# AOA-control-revC.net
KiCad netlist of a schematic drawn in EAGLE
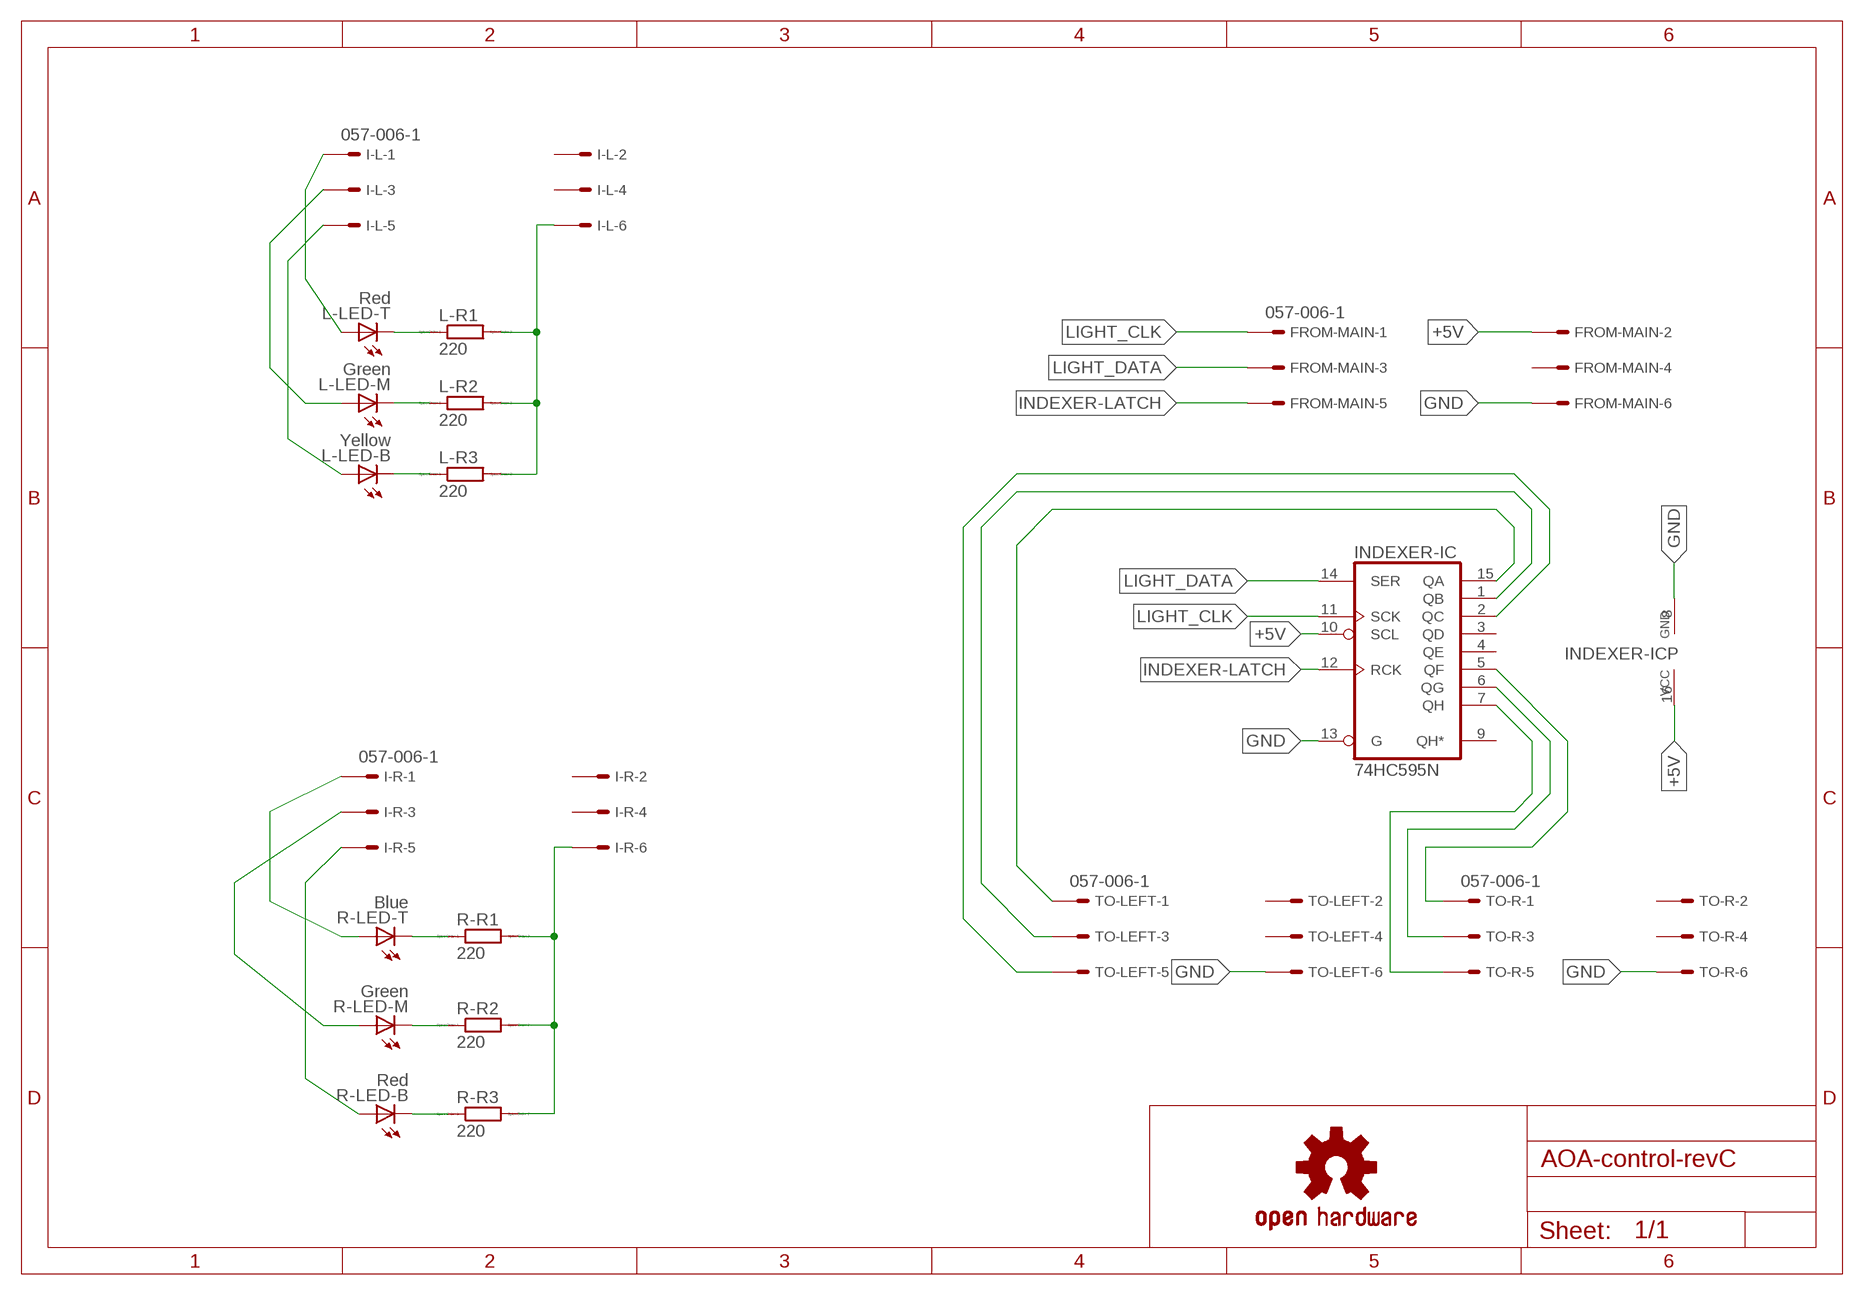
[diagram p0: schematic, sheet 1]

(export (version "E")
  (design (tool "Eeschema 10.0.6"))
  (components
    (comp (ref "FROM-MAIN")
      (value "057-006-1")
      (footprint "eagle-import:057-006-1")
      (libsource (lib "eagle-import") (part "057-006-1"))
    )
    (comp (ref "I-L")
      (value "057-006-1")
      (footprint "eagle-import:057-006-1")
      (libsource (lib "eagle-import") (part "057-006-1"))
    )
    (comp (ref "I-R")
      (value "057-006-1")
      (footprint "eagle-import:057-006-1")
      (libsource (lib "eagle-import") (part "057-006-1"))
    )
    (comp (ref "INDEXER-IC")
      (value "74HC595N")
      (footprint "eagle-import:DIL16")
      (libsource (lib "eagle-import") (part "74595NHC"))
    )
    (comp (ref "L-LED-B")
      (value "Yellow")
      (footprint "eagle-import:CP41B")
      (libsource (lib "eagle-import") (part "LED-2AC-CP41B-WGS"))
    )
    (comp (ref "L-LED-M")
      (value "Green")
      (footprint "eagle-import:CP41B")
      (libsource (lib "eagle-import") (part "LED-2AC-CP41B-WGS"))
    )
    (comp (ref "L-LED-T")
      (value "Red")
      (footprint "eagle-import:CP41B")
      (libsource (lib "eagle-import") (part "LED-2AC-CP41B-WGS"))
    )
    (comp (ref "L-R1")
      (value "220")
      (footprint "eagle-import:0204_7")
      (libsource (lib "eagle-import") (part "R0204/7"))
    )
    (comp (ref "L-R2")
      (value "220")
      (footprint "eagle-import:0204_7")
      (libsource (lib "eagle-import") (part "R0204/7"))
    )
    (comp (ref "L-R3")
      (value "220")
      (footprint "eagle-import:0204_7")
      (libsource (lib "eagle-import") (part "R0204/7"))
    )
    (comp (ref "LOGO1")
      (value "OSHW-LOGOS")
      (footprint "eagle-import:OSHW-LOGO-S")
      (libsource (lib "eagle-import") (part "OSHW-LOGOS"))
    )
    (comp (ref "R-LED-B")
      (value "Red")
      (footprint "eagle-import:CP41B")
      (libsource (lib "eagle-import") (part "LED-2AC-CP41B-WGS"))
    )
    (comp (ref "R-LED-M")
      (value "Green")
      (footprint "eagle-import:CP41B")
      (libsource (lib "eagle-import") (part "LED-2AC-CP41B-WGS"))
    )
    (comp (ref "R-LED-T")
      (value "Blue")
      (footprint "eagle-import:CP41B")
      (libsource (lib "eagle-import") (part "LED-2AC-CP41B-WGS"))
    )
    (comp (ref "R-R1")
      (value "220")
      (footprint "eagle-import:0204_7")
      (libsource (lib "eagle-import") (part "R0204/7"))
    )
    (comp (ref "R-R2")
      (value "220")
      (footprint "eagle-import:0204_7")
      (libsource (lib "eagle-import") (part "R0204/7"))
    )
    (comp (ref "R-R3")
      (value "220")
      (footprint "eagle-import:0204_7")
      (libsource (lib "eagle-import") (part "R0204/7"))
    )
    (comp (ref "TO-LEFT")
      (value "057-006-1")
      (footprint "eagle-import:057-006-1")
      (libsource (lib "eagle-import") (part "057-006-1"))
    )
    (comp (ref "TO-R")
      (value "057-006-1")
      (footprint "eagle-import:057-006-1")
      (libsource (lib "eagle-import") (part "057-006-1"))
    )
  )
  (nets
    (net (code "1") (name "+5V") (class "Default")
      (node (ref "FROM-MAIN") (pin "2") (pinfunction "S_2") (pintype "passive"))
      (node (ref "INDEXER-IC") (pin "10") (pinfunction "SCL_10") (pintype "input"))
      (node (ref "INDEXER-IC") (pin "16") (pinfunction "VCC_16") (pintype "power_in"))
    )
    (net (code "2") (name "GND") (class "Default")
      (node (ref "FROM-MAIN") (pin "6") (pinfunction "S_6") (pintype "passive"))
      (node (ref "I-L") (pin "6") (pinfunction "S_6") (pintype "passive"))
      (node (ref "I-R") (pin "6") (pinfunction "S_6") (pintype "passive"))
      (node (ref "INDEXER-IC") (pin "13") (pinfunction "G_13") (pintype "input"))
      (node (ref "INDEXER-IC") (pin "8") (pinfunction "GND_8") (pintype "power_in"))
      (node (ref "L-R1") (pin "2") (pinfunction "2_2") (pintype "passive"))
      (node (ref "L-R2") (pin "2") (pinfunction "2_2") (pintype "passive"))
      (node (ref "L-R3") (pin "2") (pinfunction "2_2") (pintype "passive"))
      (node (ref "R-R1") (pin "2") (pinfunction "2_2") (pintype "passive"))
      (node (ref "R-R2") (pin "2") (pinfunction "2_2") (pintype "passive"))
      (node (ref "R-R3") (pin "2") (pinfunction "2_2") (pintype "passive"))
      (node (ref "TO-LEFT") (pin "6") (pinfunction "S_6") (pintype "passive"))
      (node (ref "TO-R") (pin "6") (pinfunction "S_6") (pintype "passive"))
    )
    (net (code "3") (name "INDEXER-LATCH") (class "Default")
      (node (ref "FROM-MAIN") (pin "5") (pinfunction "S_5") (pintype "passive"))
      (node (ref "INDEXER-IC") (pin "12") (pinfunction "RCK_12") (pintype "input"))
    )
    (net (code "4") (name "LIGHT_CLK") (class "Default")
      (node (ref "FROM-MAIN") (pin "1") (pinfunction "S_1") (pintype "passive"))
      (node (ref "INDEXER-IC") (pin "11") (pinfunction "SCK_11") (pintype "input"))
    )
    (net (code "5") (name "LIGHT_DATA") (class "Default")
      (node (ref "FROM-MAIN") (pin "3") (pinfunction "S_3") (pintype "passive"))
      (node (ref "INDEXER-IC") (pin "14") (pinfunction "SER_14") (pintype "input"))
    )
    (net (code "6") (name "Net-(I-LA-S)") (class "Default")
      (node (ref "I-L") (pin "1") (pinfunction "S_1") (pintype "passive"))
      (node (ref "L-LED-T") (pin "2") (pinfunction "A_2") (pintype "passive"))
      (node (ref "L-LED-T") (pin "3") (pinfunction "A_3") (pintype "passive"))
    )
    (net (code "7") (name "Net-(I-LC-S)") (class "Default")
      (node (ref "I-L") (pin "3") (pinfunction "S_3") (pintype "passive"))
      (node (ref "L-LED-M") (pin "2") (pinfunction "A_2") (pintype "passive"))
      (node (ref "L-LED-M") (pin "3") (pinfunction "A_3") (pintype "passive"))
    )
    (net (code "8") (name "Net-(I-LE-S)") (class "Default")
      (node (ref "I-L") (pin "5") (pinfunction "S_5") (pintype "passive"))
      (node (ref "L-LED-B") (pin "2") (pinfunction "A_2") (pintype "passive"))
      (node (ref "L-LED-B") (pin "3") (pinfunction "A_3") (pintype "passive"))
    )
    (net (code "9") (name "Net-(I-RA-S)") (class "Default")
      (node (ref "I-R") (pin "1") (pinfunction "S_1") (pintype "passive"))
      (node (ref "R-LED-T") (pin "2") (pinfunction "A_2") (pintype "passive"))
      (node (ref "R-LED-T") (pin "3") (pinfunction "A_3") (pintype "passive"))
    )
    (net (code "10") (name "Net-(I-RC-S)") (class "Default")
      (node (ref "I-R") (pin "3") (pinfunction "S_3") (pintype "passive"))
      (node (ref "R-LED-M") (pin "2") (pinfunction "A_2") (pintype "passive"))
      (node (ref "R-LED-M") (pin "3") (pinfunction "A_3") (pintype "passive"))
    )
    (net (code "11") (name "Net-(I-RE-S)") (class "Default")
      (node (ref "I-R") (pin "5") (pinfunction "S_5") (pintype "passive"))
      (node (ref "R-LED-B") (pin "2") (pinfunction "A_2") (pintype "passive"))
      (node (ref "R-LED-B") (pin "3") (pinfunction "A_3") (pintype "passive"))
    )
    (net (code "12") (name "Net-(INDEXER-ICA-QA)") (class "Default")
      (node (ref "INDEXER-IC") (pin "15") (pinfunction "QA_15") (pintype "tri_state"))
      (node (ref "TO-LEFT") (pin "1") (pinfunction "S_1") (pintype "passive"))
    )
    (net (code "13") (name "Net-(INDEXER-ICA-QB)") (class "Default")
      (node (ref "INDEXER-IC") (pin "1") (pinfunction "QB_1") (pintype "tri_state"))
      (node (ref "TO-LEFT") (pin "3") (pinfunction "S_3") (pintype "passive"))
    )
    (net (code "14") (name "Net-(INDEXER-ICA-QC)") (class "Default")
      (node (ref "INDEXER-IC") (pin "2") (pinfunction "QC_2") (pintype "tri_state"))
      (node (ref "TO-LEFT") (pin "5") (pinfunction "S_5") (pintype "passive"))
    )
    (net (code "15") (name "Net-(INDEXER-ICA-QF)") (class "Default")
      (node (ref "INDEXER-IC") (pin "5") (pinfunction "QF_5") (pintype "tri_state"))
      (node (ref "TO-R") (pin "1") (pinfunction "S_1") (pintype "passive"))
    )
    (net (code "16") (name "Net-(INDEXER-ICA-QG)") (class "Default")
      (node (ref "INDEXER-IC") (pin "6") (pinfunction "QG_6") (pintype "tri_state"))
      (node (ref "TO-R") (pin "3") (pinfunction "S_3") (pintype "passive"))
    )
    (net (code "17") (name "Net-(INDEXER-ICA-QH)") (class "Default")
      (node (ref "INDEXER-IC") (pin "7") (pinfunction "QH_7") (pintype "tri_state"))
      (node (ref "TO-R") (pin "5") (pinfunction "S_5") (pintype "passive"))
    )
    (net (code "18") (name "Net-(L-LED-B-C-Pad1)") (class "Default")
      (node (ref "L-LED-B") (pin "1") (pinfunction "C_1") (pintype "passive"))
      (node (ref "L-LED-B") (pin "4") (pinfunction "C_4") (pintype "passive"))
      (node (ref "L-R3") (pin "1") (pinfunction "1_1") (pintype "passive"))
    )
    (net (code "19") (name "Net-(L-LED-M-C-Pad1)") (class "Default")
      (node (ref "L-LED-M") (pin "1") (pinfunction "C_1") (pintype "passive"))
      (node (ref "L-LED-M") (pin "4") (pinfunction "C_4") (pintype "passive"))
      (node (ref "L-R2") (pin "1") (pinfunction "1_1") (pintype "passive"))
    )
    (net (code "20") (name "Net-(L-LED-T-C-Pad1)") (class "Default")
      (node (ref "L-LED-T") (pin "1") (pinfunction "C_1") (pintype "passive"))
      (node (ref "L-LED-T") (pin "4") (pinfunction "C_4") (pintype "passive"))
      (node (ref "L-R1") (pin "1") (pinfunction "1_1") (pintype "passive"))
    )
    (net (code "21") (name "Net-(R-LED-B-C-Pad1)") (class "Default")
      (node (ref "R-LED-B") (pin "1") (pinfunction "C_1") (pintype "passive"))
      (node (ref "R-LED-B") (pin "4") (pinfunction "C_4") (pintype "passive"))
      (node (ref "R-R3") (pin "1") (pinfunction "1_1") (pintype "passive"))
    )
    (net (code "22") (name "Net-(R-LED-M-C-Pad1)") (class "Default")
      (node (ref "R-LED-M") (pin "1") (pinfunction "C_1") (pintype "passive"))
      (node (ref "R-LED-M") (pin "4") (pinfunction "C_4") (pintype "passive"))
      (node (ref "R-R2") (pin "1") (pinfunction "1_1") (pintype "passive"))
    )
    (net (code "23") (name "Net-(R-LED-T-C-Pad1)") (class "Default")
      (node (ref "R-LED-T") (pin "1") (pinfunction "C_1") (pintype "passive"))
      (node (ref "R-LED-T") (pin "4") (pinfunction "C_4") (pintype "passive"))
      (node (ref "R-R1") (pin "1") (pinfunction "1_1") (pintype "passive"))
    )
    (net (code "24") (name "unconnected-(FROM-MAIND-S-Pad4)") (class "Default")
      (node (ref "FROM-MAIN") (pin "4") (pinfunction "S_4") (pintype "passive"))
    )
    (net (code "25") (name "unconnected-(I-LB-S-Pad2)") (class "Default")
      (node (ref "I-L") (pin "2") (pinfunction "S_2") (pintype "passive"))
    )
    (net (code "26") (name "unconnected-(I-LD-S-Pad4)") (class "Default")
      (node (ref "I-L") (pin "4") (pinfunction "S_4") (pintype "passive"))
    )
    (net (code "27") (name "unconnected-(I-RB-S-Pad2)") (class "Default")
      (node (ref "I-R") (pin "2") (pinfunction "S_2") (pintype "passive"))
    )
    (net (code "28") (name "unconnected-(I-RD-S-Pad4)") (class "Default")
      (node (ref "I-R") (pin "4") (pinfunction "S_4") (pintype "passive"))
    )
    (net (code "29") (name "unconnected-(INDEXER-ICA-QD-Pad3)") (class "Default")
      (node (ref "INDEXER-IC") (pin "3") (pinfunction "QD_3") (pintype "tri_state"))
    )
    (net (code "30") (name "unconnected-(INDEXER-ICA-QE-Pad4)") (class "Default")
      (node (ref "INDEXER-IC") (pin "4") (pinfunction "QE_4") (pintype "tri_state"))
    )
    (net (code "31") (name "unconnected-(INDEXER-ICA-QH*-Pad9)") (class "Default")
      (node (ref "INDEXER-IC") (pin "9") (pinfunction "QH*_9") (pintype "tri_state"))
    )
    (net (code "32") (name "unconnected-(TO-LEFTB-S-Pad2)") (class "Default")
      (node (ref "TO-LEFT") (pin "2") (pinfunction "S_2") (pintype "passive"))
    )
    (net (code "33") (name "unconnected-(TO-LEFTD-S-Pad4)") (class "Default")
      (node (ref "TO-LEFT") (pin "4") (pinfunction "S_4") (pintype "passive"))
    )
    (net (code "34") (name "unconnected-(TO-RB-S-Pad2)") (class "Default")
      (node (ref "TO-R") (pin "2") (pinfunction "S_2") (pintype "passive"))
    )
    (net (code "35") (name "unconnected-(TO-RD-S-Pad4)") (class "Default")
      (node (ref "TO-R") (pin "4") (pinfunction "S_4") (pintype "passive"))
    )
  )
)
